# contactor_control.net
KiCad netlist of a schematic drawn in Altium Designer
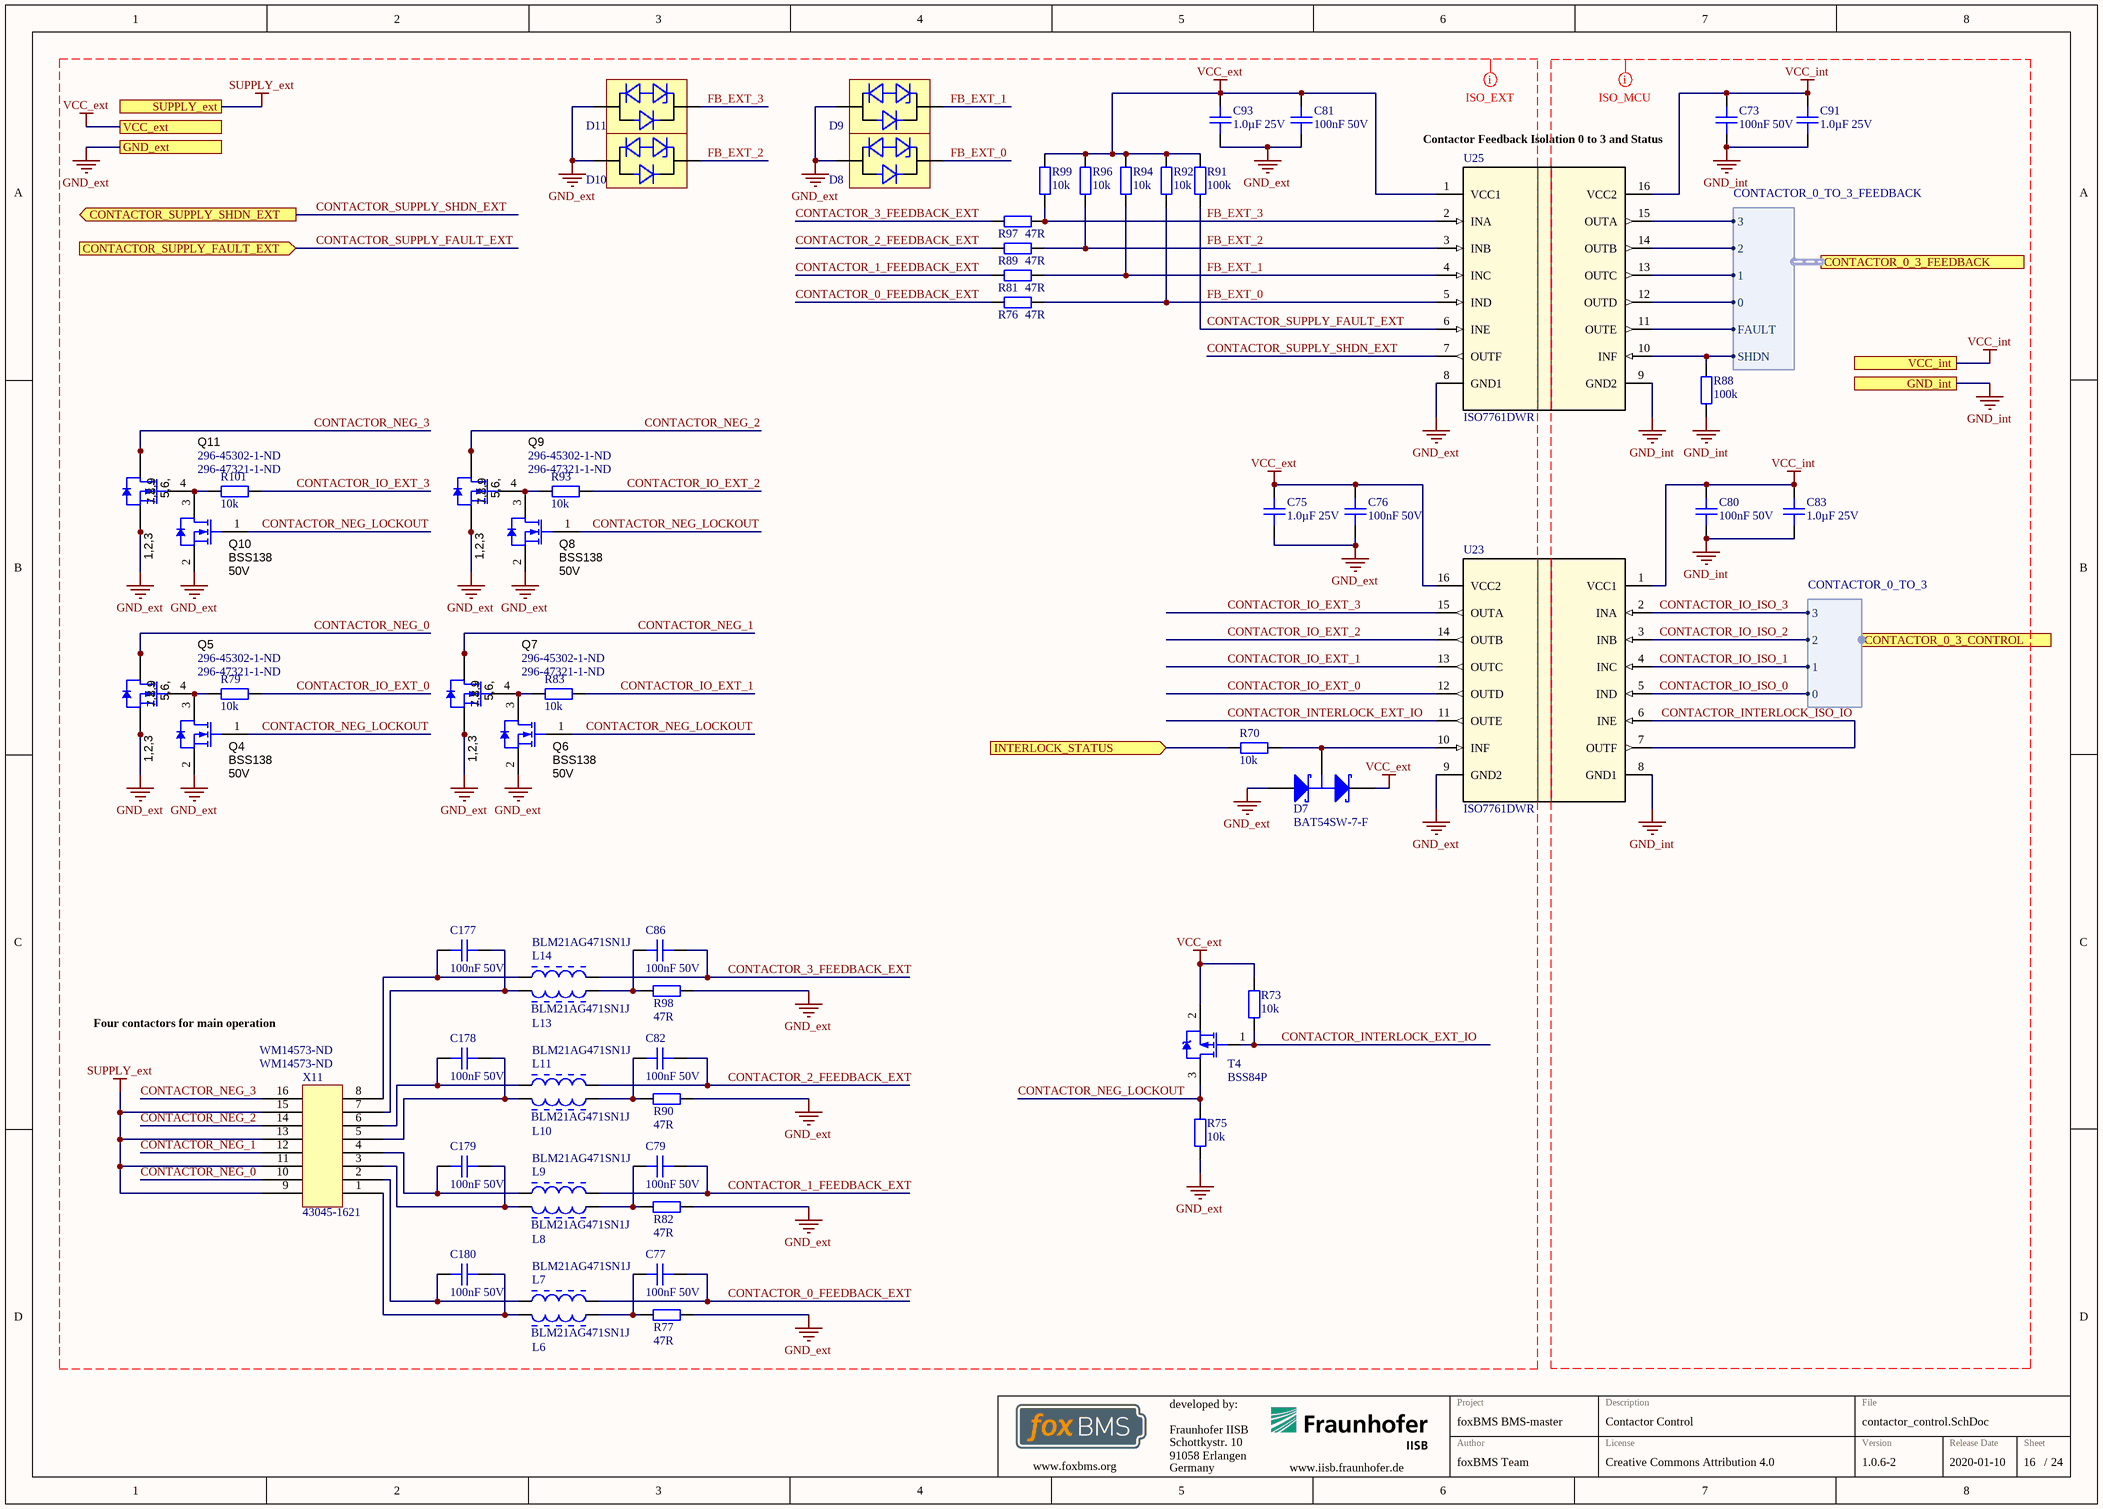
[diagram p0: contactor_control.SchDoc]

(export (version "E")
  (design (tool "Eeschema 10.0.6"))
  (components
    (comp (ref "C73")
      (value "100nF 50V")
      (footprint "0603C")
      (description "Ceramic, 100nF, ±10%, 50V, X7R, –55 to 125°C, 0603 (1608),RoHS, Automotive")
      (fields (field (name "PART NUMBER") "GCJ188R71H104KA12") (field (name "TOLERANCE") "±10%"))
      (libsource (lib "master-010106") (part "C"))
    )
    (comp (ref "C75")
      (value "1.0µF 25V")
      (footprint "0603C")
      (description "Ceramic, 1.0µF, ±10%, 25V, X7R, –55 to 125°C, 0603 (1608),RoHS, Automotive")
      (fields (field (name "PART NUMBER") "GCJ188R71E105KA01") (field (name "TOLERANCE") "±10%"))
      (libsource (lib "master-010106") (part "gen_C_ceramic_1u_25V_X7R_0603"))
    )
    (comp (ref "C76")
      (value "100nF 50V")
      (footprint "0603C")
      (description "Ceramic, 100nF, ±10%, 50V, X7R, –55 to 125°C, 0603 (1608),RoHS, Automotive")
      (fields (field (name "PART NUMBER") "GCJ188R71H104KA12") (field (name "TOLERANCE") "±10%"))
      (libsource (lib "master-010106") (part "C"))
    )
    (comp (ref "C77")
      (value "100nF 50V")
      (footprint "0603C")
      (description "Ceramic, 100nF, ±10%, 50V, X7R, –55 to 125°C, 0603 (1608),RoHS, Automotive")
      (fields (field (name "PART NUMBER") "GCJ188R71H104KA12") (field (name "TOLERANCE") "±10%"))
      (libsource (lib "master-010106") (part "C"))
    )
    (comp (ref "C79")
      (value "100nF 50V")
      (footprint "0603C")
      (description "Ceramic, 100nF, ±10%, 50V, X7R, –55 to 125°C, 0603 (1608),RoHS, Automotive")
      (fields (field (name "PART NUMBER") "GCJ188R71H104KA12") (field (name "TOLERANCE") "±10%"))
      (libsource (lib "master-010106") (part "C"))
    )
    (comp (ref "C80")
      (value "100nF 50V")
      (footprint "0603C")
      (description "Ceramic, 100nF, ±10%, 50V, X7R, –55 to 125°C, 0603 (1608),RoHS, Automotive")
      (fields (field (name "PART NUMBER") "GCJ188R71H104KA12") (field (name "TOLERANCE") "±10%"))
      (libsource (lib "master-010106") (part "C"))
    )
    (comp (ref "C81")
      (value "100nF 50V")
      (footprint "0603C")
      (description "Ceramic, 100nF, ±10%, 50V, X7R, –55 to 125°C, 0603 (1608),RoHS, Automotive")
      (fields (field (name "PART NUMBER") "GCJ188R71H104KA12") (field (name "TOLERANCE") "±10%"))
      (libsource (lib "master-010106") (part "C"))
    )
    (comp (ref "C82")
      (value "100nF 50V")
      (footprint "0603C")
      (description "Ceramic, 100nF, ±10%, 50V, X7R, –55 to 125°C, 0603 (1608),RoHS, Automotive")
      (fields (field (name "PART NUMBER") "GCJ188R71H104KA12") (field (name "TOLERANCE") "±10%"))
      (libsource (lib "master-010106") (part "C"))
    )
    (comp (ref "C83")
      (value "1.0µF 25V")
      (footprint "0603C")
      (description "Ceramic, 1.0µF, ±10%, 25V, X7R, –55 to 125°C, 0603 (1608),RoHS, Automotive")
      (fields (field (name "PART NUMBER") "GCJ188R71E105KA01") (field (name "TOLERANCE") "±10%"))
      (libsource (lib "master-010106") (part "gen_C_ceramic_1u_25V_X7R_0603"))
    )
    (comp (ref "C86")
      (value "100nF 50V")
      (footprint "0603C")
      (description "Ceramic, 100nF, ±10%, 50V, X7R, –55 to 125°C, 0603 (1608),RoHS, Automotive")
      (fields (field (name "PART NUMBER") "GCJ188R71H104KA12") (field (name "TOLERANCE") "±10%"))
      (libsource (lib "master-010106") (part "C"))
    )
    (comp (ref "C91")
      (value "1.0µF 25V")
      (footprint "0603C")
      (description "Ceramic, 1.0µF, ±10%, 25V, X7R, –55 to 125°C, 0603 (1608),RoHS, Automotive")
      (fields (field (name "PART NUMBER") "GCJ188R71E105KA01") (field (name "TOLERANCE") "±10%"))
      (libsource (lib "master-010106") (part "gen_C_ceramic_1u_25V_X7R_0603"))
    )
    (comp (ref "C93")
      (value "1.0µF 25V")
      (footprint "0603C")
      (description "Ceramic, 1.0µF, ±10%, 25V, X7R, –55 to 125°C, 0603 (1608),RoHS, Automotive")
      (fields (field (name "PART NUMBER") "GCJ188R71E105KA01") (field (name "TOLERANCE") "±10%"))
      (libsource (lib "master-010106") (part "gen_C_ceramic_1u_25V_X7R_0603"))
    )
    (comp (ref "C177")
      (value "100nF 50V")
      (footprint "0603C")
      (description "Ceramic, 100nF, ±10%, 50V, X7R, –55 to 125°C, 0603 (1608),RoHS, Automotive")
      (fields (field (name "PART NUMBER") "GCJ188R71H104KA12") (field (name "TOLERANCE") "±10%"))
      (libsource (lib "master-010106") (part "C"))
    )
    (comp (ref "C178")
      (value "100nF 50V")
      (footprint "0603C")
      (description "Ceramic, 100nF, ±10%, 50V, X7R, –55 to 125°C, 0603 (1608),RoHS, Automotive")
      (fields (field (name "PART NUMBER") "GCJ188R71H104KA12") (field (name "TOLERANCE") "±10%"))
      (libsource (lib "master-010106") (part "C"))
    )
    (comp (ref "C179")
      (value "100nF 50V")
      (footprint "0603C")
      (description "Ceramic, 100nF, ±10%, 50V, X7R, –55 to 125°C, 0603 (1608),RoHS, Automotive")
      (fields (field (name "PART NUMBER") "GCJ188R71H104KA12") (field (name "TOLERANCE") "±10%"))
      (libsource (lib "master-010106") (part "C"))
    )
    (comp (ref "C180")
      (value "100nF 50V")
      (footprint "0603C")
      (description "Ceramic, 100nF, ±10%, 50V, X7R, –55 to 125°C, 0603 (1608),RoHS, Automotive")
      (fields (field (name "PART NUMBER") "GCJ188R71H104KA12") (field (name "TOLERANCE") "±10%"))
      (libsource (lib "master-010106") (part "C"))
    )
    (comp (ref "D7")
      (value "BAT54SW-7-F")
      (footprint "DIOD-SOT323-3_V")
      (description "Schottky Barrier Diode, 30 V, 200 mA, -65 to 125 degC, 3-Pin SOT323, RoHS, Tape and Reel")
      (fields (field (name "MANUFACTURER") "DiodesIncorporated"))
      (libsource (lib "Altium Content Vault") (part "DSKY-AKC-3"))
    )
    (comp (ref "D8")
      (value "CDSOD323-T05")
      (footprint "SODFL250X110-2N")
      (description "TVS Diode, CDSOD323 Series, Unidirectional, 5 V, 18.3 V, SOD-323, 2 Pins")
      (fields (field (name "MANUFACTURER") "Bourns"))
      (libsource (lib "OE750") (part "D_TVS_uni"))
    )
    (comp (ref "D9")
      (value "CDSOD323-T05")
      (footprint "SODFL250X110-2N")
      (description "TVS Diode, CDSOD323 Series, Unidirectional, 5 V, 18.3 V, SOD-323, 2 Pins")
      (fields (field (name "MANUFACTURER") "Bourns"))
      (libsource (lib "OE750") (part "D_TVS_uni"))
    )
    (comp (ref "D10")
      (value "CDSOD323-T05")
      (footprint "SODFL250X110-2N")
      (description "TVS Diode, CDSOD323 Series, Unidirectional, 5 V, 18.3 V, SOD-323, 2 Pins")
      (fields (field (name "MANUFACTURER") "Bourns"))
      (libsource (lib "OE750") (part "D_TVS_uni"))
    )
    (comp (ref "D11")
      (value "CDSOD323-T05")
      (footprint "SODFL250X110-2N")
      (description "TVS Diode, CDSOD323 Series, Unidirectional, 5 V, 18.3 V, SOD-323, 2 Pins")
      (fields (field (name "MANUFACTURER") "Bourns"))
      (libsource (lib "OE750") (part "D_TVS_uni"))
    )
    (comp (ref "L6")
      (value "BLM21AG471SN1J")
      (footprint "MURA-BLM21-H1-CHIP-2_V")
      (fields (field (name "MANUFACTURER") "Murata"))
      (libsource (lib "") (part "MURA-FB-2_1"))
    )
    (comp (ref "L7")
      (value "BLM21AG471SN1J")
      (footprint "MURA-BLM21-H1-CHIP-2_V")
      (fields (field (name "MANUFACTURER") "Murata"))
      (libsource (lib "Altium Content Vault") (part "MURA-FB-2"))
    )
    (comp (ref "L8")
      (value "BLM21AG471SN1J")
      (footprint "MURA-BLM21-H1-CHIP-2_V")
      (fields (field (name "MANUFACTURER") "Murata"))
      (libsource (lib "") (part "MURA-FB-2_1"))
    )
    (comp (ref "L9")
      (value "BLM21AG471SN1J")
      (footprint "MURA-BLM21-H1-CHIP-2_V")
      (fields (field (name "MANUFACTURER") "Murata"))
      (libsource (lib "Altium Content Vault") (part "MURA-FB-2"))
    )
    (comp (ref "L10")
      (value "BLM21AG471SN1J")
      (footprint "MURA-BLM21-H1-CHIP-2_V")
      (fields (field (name "MANUFACTURER") "Murata"))
      (libsource (lib "") (part "MURA-FB-2_1"))
    )
    (comp (ref "L11")
      (value "BLM21AG471SN1J")
      (footprint "MURA-BLM21-H1-CHIP-2_V")
      (fields (field (name "MANUFACTURER") "Murata"))
      (libsource (lib "Altium Content Vault") (part "MURA-FB-2"))
    )
    (comp (ref "L13")
      (value "BLM21AG471SN1J")
      (footprint "MURA-BLM21-H1-CHIP-2_V")
      (fields (field (name "MANUFACTURER") "Murata"))
      (libsource (lib "") (part "MURA-FB-2_1"))
    )
    (comp (ref "L14")
      (value "BLM21AG471SN1J")
      (footprint "MURA-BLM21-H1-CHIP-2_V")
      (fields (field (name "MANUFACTURER") "Murata"))
      (libsource (lib "Altium Content Vault") (part "MURA-FB-2"))
    )
    (comp (ref "Q4")
      (value "BSS138")
      (footprint "SOT-23")
      (description "MOSFET, N-CH, 50V, 0.22A, SOT-23")
      (fields
        (field (name "MANUFACTURER") "Fairchild Semiconductor")
        (field (name "ALTIUM_VALUE") "50V")
        (field (name "PUBLISHER") "Texas Instruments")
      )
      (libsource (lib "master-010106") (part "BSS138"))
    )
    (comp (ref "Q5")
      (value "CSD18543Q3A")
      (footprint "SONQ3A")
      (description "60V, N ch NexFET MOSFET™, single SON3x3, 9.9mOhm")
      (fields
        (field (name "MANUFACTURER") "Texas Instruments")
        (field (name "SUPPLIER PART NUMBER 1") "296-45302-1-ND")
        (field (name "SUPPLIER PART NUMBER 2") "296-47321-1-ND")
        (field (name "PUBLISHER") "Texas Instruments")
      )
      (libsource (lib "master-010106") (part "CSD18543Q3A"))
    )
    (comp (ref "Q6")
      (value "BSS138")
      (footprint "SOT-23")
      (description "MOSFET, N-CH, 50V, 0.22A, SOT-23")
      (fields
        (field (name "MANUFACTURER") "Fairchild Semiconductor")
        (field (name "ALTIUM_VALUE") "50V")
        (field (name "PUBLISHER") "Texas Instruments")
      )
      (libsource (lib "master-010106") (part "BSS138"))
    )
    (comp (ref "Q7")
      (value "CSD18543Q3A")
      (footprint "SONQ3A")
      (description "60V, N ch NexFET MOSFET™, single SON3x3, 9.9mOhm")
      (fields
        (field (name "MANUFACTURER") "Texas Instruments")
        (field (name "SUPPLIER PART NUMBER 1") "296-45302-1-ND")
        (field (name "SUPPLIER PART NUMBER 2") "296-47321-1-ND")
        (field (name "PUBLISHER") "Texas Instruments")
      )
      (libsource (lib "master-010106") (part "CSD18543Q3A"))
    )
    (comp (ref "Q8")
      (value "BSS138")
      (footprint "SOT-23")
      (description "MOSFET, N-CH, 50V, 0.22A, SOT-23")
      (fields
        (field (name "MANUFACTURER") "Fairchild Semiconductor")
        (field (name "ALTIUM_VALUE") "50V")
        (field (name "PUBLISHER") "Texas Instruments")
      )
      (libsource (lib "master-010106") (part "BSS138"))
    )
    (comp (ref "Q9")
      (value "CSD18543Q3A")
      (footprint "SONQ3A")
      (description "60V, N ch NexFET MOSFET™, single SON3x3, 9.9mOhm")
      (fields
        (field (name "MANUFACTURER") "Texas Instruments")
        (field (name "SUPPLIER PART NUMBER 1") "296-45302-1-ND")
        (field (name "SUPPLIER PART NUMBER 2") "296-47321-1-ND")
        (field (name "PUBLISHER") "Texas Instruments")
      )
      (libsource (lib "master-010106") (part "CSD18543Q3A"))
    )
    (comp (ref "Q10")
      (value "BSS138")
      (footprint "SOT-23")
      (description "MOSFET, N-CH, 50V, 0.22A, SOT-23")
      (fields
        (field (name "MANUFACTURER") "Fairchild Semiconductor")
        (field (name "ALTIUM_VALUE") "50V")
        (field (name "PUBLISHER") "Texas Instruments")
      )
      (libsource (lib "master-010106") (part "BSS138"))
    )
    (comp (ref "Q11")
      (value "CSD18543Q3A")
      (footprint "SONQ3A")
      (description "60V, N ch NexFET MOSFET™, single SON3x3, 9.9mOhm")
      (fields
        (field (name "MANUFACTURER") "Texas Instruments")
        (field (name "SUPPLIER PART NUMBER 1") "296-45302-1-ND")
        (field (name "SUPPLIER PART NUMBER 2") "296-47321-1-ND")
        (field (name "PUBLISHER") "Texas Instruments")
      )
      (libsource (lib "master-010106") (part "CSD18543Q3A"))
    )
    (comp (ref "R70")
      (value "10k")
      (footprint "0603R")
      (description "SMD Resistor 10k 0603")
      (fields (field (name "PART NUMBER") "gen_R_10k_0603") (field (name "TOLERANCE") "1%"))
      (libsource (lib "master-010106") (part "R"))
    )
    (comp (ref "R73")
      (value "10k")
      (footprint "0603R")
      (description "SMD Resistor 10k 0603")
      (fields (field (name "PART NUMBER") "gen_R_10k_0603") (field (name "TOLERANCE") "1%"))
      (libsource (lib "master-010106") (part "R"))
    )
    (comp (ref "R75")
      (value "10k")
      (footprint "0603R")
      (description "SMD Resistor 10k 0603")
      (fields (field (name "PART NUMBER") "gen_R_10k_0603") (field (name "TOLERANCE") "1%"))
      (libsource (lib "master-010106") (part "R"))
    )
    (comp (ref "R76")
      (value "47R")
      (footprint "0603R")
      (description "SMD Resistor 47R 0603")
      (fields (field (name "PART NUMBER") "gen_R_47R_0603") (field (name "TOLERANCE") "1%"))
      (libsource (lib "master-010106") (part "R"))
    )
    (comp (ref "R77")
      (value "47R")
      (footprint "0603R")
      (description "SMD Resistor 47R 0603")
      (fields (field (name "PART NUMBER") "gen_R_47R_0603") (field (name "TOLERANCE") "1%"))
      (libsource (lib "master-010106") (part "R"))
    )
    (comp (ref "R79")
      (value "10k")
      (footprint "0603R")
      (description "SMD Resistor 10k 0603")
      (fields (field (name "PART NUMBER") "gen_R_10k_0603") (field (name "TOLERANCE") "1%"))
      (libsource (lib "master-010106") (part "R"))
    )
    (comp (ref "R81")
      (value "47R")
      (footprint "0603R")
      (description "SMD Resistor 47R 0603")
      (fields (field (name "PART NUMBER") "gen_R_47R_0603") (field (name "TOLERANCE") "1%"))
      (libsource (lib "master-010106") (part "R"))
    )
    (comp (ref "R82")
      (value "47R")
      (footprint "0603R")
      (description "SMD Resistor 47R 0603")
      (fields (field (name "PART NUMBER") "gen_R_47R_0603") (field (name "TOLERANCE") "1%"))
      (libsource (lib "master-010106") (part "R"))
    )
    (comp (ref "R83")
      (value "10k")
      (footprint "0603R")
      (description "SMD Resistor 10k 0603")
      (fields (field (name "PART NUMBER") "gen_R_10k_0603") (field (name "TOLERANCE") "1%"))
      (libsource (lib "master-010106") (part "R"))
    )
    (comp (ref "R88")
      (value "100k")
      (footprint "0603R")
      (description "SMD Resistor 100k 0603")
      (fields (field (name "PART NUMBER") "gen_R_100k_0603"))
      (libsource (lib "master-010106") (part "gen_R_100k_0603"))
    )
    (comp (ref "R89")
      (value "47R")
      (footprint "0603R")
      (description "SMD Resistor 47R 0603")
      (fields (field (name "PART NUMBER") "gen_R_47R_0603") (field (name "TOLERANCE") "1%"))
      (libsource (lib "master-010106") (part "R"))
    )
    (comp (ref "R90")
      (value "47R")
      (footprint "0603R")
      (description "SMD Resistor 47R 0603")
      (fields (field (name "PART NUMBER") "gen_R_47R_0603") (field (name "TOLERANCE") "1%"))
      (libsource (lib "master-010106") (part "R"))
    )
    (comp (ref "R91")
      (value "100k")
      (footprint "0603R")
      (description "SMD Resistor 100k 0603")
      (fields (field (name "PART NUMBER") "gen_R_100k_0603"))
      (libsource (lib "master-010106") (part "gen_R_100k_0603"))
    )
    (comp (ref "R92")
      (value "10k")
      (footprint "0603R")
      (description "SMD Resistor 10k 0603")
      (fields (field (name "PART NUMBER") "gen_R_10k_0603") (field (name "TOLERANCE") "1%"))
      (libsource (lib "master-010106") (part "R"))
    )
    (comp (ref "R93")
      (value "10k")
      (footprint "0603R")
      (description "SMD Resistor 10k 0603")
      (fields (field (name "PART NUMBER") "gen_R_10k_0603") (field (name "TOLERANCE") "1%"))
      (libsource (lib "master-010106") (part "R"))
    )
    (comp (ref "R94")
      (value "10k")
      (footprint "0603R")
      (description "SMD Resistor 10k 0603")
      (fields (field (name "PART NUMBER") "gen_R_10k_0603") (field (name "TOLERANCE") "1%"))
      (libsource (lib "master-010106") (part "R"))
    )
    (comp (ref "R96")
      (value "10k")
      (footprint "0603R")
      (description "SMD Resistor 10k 0603")
      (fields (field (name "PART NUMBER") "gen_R_10k_0603") (field (name "TOLERANCE") "1%"))
      (libsource (lib "master-010106") (part "R"))
    )
    (comp (ref "R97")
      (value "47R")
      (footprint "0603R")
      (description "SMD Resistor 47R 0603")
      (fields (field (name "PART NUMBER") "gen_R_47R_0603") (field (name "TOLERANCE") "1%"))
      (libsource (lib "master-010106") (part "R"))
    )
    (comp (ref "R98")
      (value "47R")
      (footprint "0603R")
      (description "SMD Resistor 47R 0603")
      (fields (field (name "PART NUMBER") "gen_R_47R_0603") (field (name "TOLERANCE") "1%"))
      (libsource (lib "master-010106") (part "R"))
    )
    (comp (ref "R99")
      (value "10k")
      (footprint "0603R")
      (description "SMD Resistor 10k 0603")
      (fields (field (name "PART NUMBER") "gen_R_10k_0603") (field (name "TOLERANCE") "1%"))
      (libsource (lib "master-010106") (part "R"))
    )
    (comp (ref "R101")
      (value "10k")
      (footprint "0603R")
      (description "SMD Resistor 10k 0603")
      (fields (field (name "PART NUMBER") "gen_R_10k_0603") (field (name "TOLERANCE") "1%"))
      (libsource (lib "master-010106") (part "R"))
    )
    (comp (ref "T4")
      (value "BSS84P")
      (footprint "INF-PG-SOT23_N")
      (fields (field (name "MANUFACTURER") "Infineon"))
      (libsource (lib "Altium Content Vault") (part "INF-PEMOS-GSD-3-B"))
    )
    (comp (ref "U23")
      (value "ISO7761DWR")
      (footprint "DW0016B_N")
      (description "Imported")
      (fields (field (name "MANUFACTURER") "Texas Instruments"))
      (libsource (lib "ti-import") (part "ISO7761DWR"))
    )
    (comp (ref "U25")
      (value "ISO7761DWR")
      (footprint "DW0016B_N")
      (description "Imported")
      (fields (field (name "MANUFACTURER") "Texas Instruments"))
      (libsource (lib "") (part "ISO7761DWR_1"))
    )
    (comp (ref "X11")
      (value "43045-1621")
      (footprint "43045-1621")
      (fields
        (field (name "PART NUMBER") "molex_microfit_3_08x2_THT")
        (field (name "MANUFACTURER") "Molex")
        (field (name "SUPPLIER PART NUMBER 1") "WM14573-ND")
        (field (name "SUPPLIER PART NUMBER 2") "WM14573-ND")
      )
      (libsource (lib "master-010106") (part "molex_microfit_3_08x2_THT"))
    )
  )
  (nets
    (net (code "3") (name "/CONTACTOR_0_FEEDBACK_EXT") (class "Default")
      (node (ref "C77") (pin "2") (pinfunction "2_2") (pintype "passive"))
      (node (ref "L7") (pin "2") (pinfunction "2_2") (pintype "passive"))
      (node (ref "R76") (pin "1") (pinfunction "1_1") (pintype "passive"))
    )
    (net (code "4") (name "/CONTACTOR_1_FEEDBACK_EXT") (class "Default")
      (node (ref "C79") (pin "2") (pinfunction "2_2") (pintype "passive"))
      (node (ref "L9") (pin "2") (pinfunction "2_2") (pintype "passive"))
      (node (ref "R81") (pin "1") (pinfunction "1_1") (pintype "passive"))
    )
    (net (code "5") (name "/CONTACTOR_2_FEEDBACK_EXT") (class "Default")
      (node (ref "C82") (pin "2") (pinfunction "2_2") (pintype "passive"))
      (node (ref "L11") (pin "2") (pinfunction "2_2") (pintype "passive"))
      (node (ref "R89") (pin "1") (pinfunction "1_1") (pintype "passive"))
    )
    (net (code "6") (name "/CONTACTOR_3_FEEDBACK_EXT") (class "Default")
      (node (ref "C86") (pin "2") (pinfunction "2_2") (pintype "passive"))
      (node (ref "L14") (pin "2") (pinfunction "2_2") (pintype "passive"))
      (node (ref "R97") (pin "2") (pinfunction "2_2") (pintype "passive"))
    )
    (net (code "7") (name "/CONTACTOR_INTERLOCK_EXT_IO") (class "Default")
      (node (ref "R73") (pin "1") (pinfunction "1_1") (pintype "passive"))
      (node (ref "T4") (pin "1") (pinfunction "GATE_1") (pintype "passive"))
      (node (ref "U23") (pin "11") (pinfunction "OUTE_11") (pintype "output"))
    )
    (net (code "8") (name "/CONTACTOR_INTERLOCK_ISO_IO") (class "Default")
      (node (ref "U23") (pin "6") (pinfunction "INE_6") (pintype "input"))
      (node (ref "U23") (pin "7") (pinfunction "OUTF_7") (pintype "output"))
    )
    (net (code "9") (name "/CONTACTOR_IO_EXT_0") (class "Default")
      (node (ref "R79") (pin "1") (pinfunction "1_1") (pintype "passive"))
      (node (ref "U23") (pin "12") (pinfunction "OUTD_12") (pintype "output"))
    )
    (net (code "10") (name "/CONTACTOR_IO_EXT_1") (class "Default")
      (node (ref "R83") (pin "1") (pinfunction "1_1") (pintype "passive"))
      (node (ref "U23") (pin "13") (pinfunction "OUTC_13") (pintype "output"))
    )
    (net (code "11") (name "/CONTACTOR_IO_EXT_2") (class "Default")
      (node (ref "R93") (pin "1") (pinfunction "1_1") (pintype "passive"))
      (node (ref "U23") (pin "14") (pinfunction "OUTB_14") (pintype "output"))
    )
    (net (code "12") (name "/CONTACTOR_IO_EXT_3") (class "Default")
      (node (ref "R101") (pin "1") (pinfunction "1_1") (pintype "passive"))
      (node (ref "U23") (pin "15") (pinfunction "OUTA_15") (pintype "output"))
    )
    (net (code "13") (name "/CONTACTOR_IO_ISO_0") (class "Default")
      (node (ref "U23") (pin "5") (pinfunction "IND_5") (pintype "input"))
    )
    (net (code "14") (name "/CONTACTOR_IO_ISO_1") (class "Default")
      (node (ref "U23") (pin "4") (pinfunction "INC_4") (pintype "input"))
    )
    (net (code "15") (name "/CONTACTOR_IO_ISO_2") (class "Default")
      (node (ref "U23") (pin "3") (pinfunction "INB_3") (pintype "input"))
    )
    (net (code "16") (name "/CONTACTOR_IO_ISO_3") (class "Default")
      (node (ref "U23") (pin "2") (pinfunction "INA_2") (pintype "input"))
    )
    (net (code "17") (name "/CONTACTOR_NEG_0") (class "Default")
      (node (ref "Q5") (pin "5") (pinfunction "D_5") (pintype "passive"))
      (node (ref "Q5") (pin "6") (pinfunction "D_6") (pintype "passive"))
      (node (ref "Q5") (pin "7") (pinfunction "D_7") (pintype "passive"))
      (node (ref "Q5") (pin "8") (pinfunction "D_8") (pintype "passive"))
      (node (ref "Q5") (pin "9") (pinfunction "D_9") (pintype "passive"))
      (node (ref "X11") (pin "10") (pintype "passive"))
    )
    (net (code "18") (name "/CONTACTOR_NEG_1") (class "Default")
      (node (ref "Q7") (pin "5") (pinfunction "D_5") (pintype "passive"))
      (node (ref "Q7") (pin "6") (pinfunction "D_6") (pintype "passive"))
      (node (ref "Q7") (pin "7") (pinfunction "D_7") (pintype "passive"))
      (node (ref "Q7") (pin "8") (pinfunction "D_8") (pintype "passive"))
      (node (ref "Q7") (pin "9") (pinfunction "D_9") (pintype "passive"))
      (node (ref "X11") (pin "12") (pintype "passive"))
    )
    (net (code "19") (name "/CONTACTOR_NEG_2") (class "Default")
      (node (ref "Q9") (pin "5") (pinfunction "D_5") (pintype "passive"))
      (node (ref "Q9") (pin "6") (pinfunction "D_6") (pintype "passive"))
      (node (ref "Q9") (pin "7") (pinfunction "D_7") (pintype "passive"))
      (node (ref "Q9") (pin "8") (pinfunction "D_8") (pintype "passive"))
      (node (ref "Q9") (pin "9") (pinfunction "D_9") (pintype "passive"))
      (node (ref "X11") (pin "14") (pintype "passive"))
    )
    (net (code "20") (name "/CONTACTOR_NEG_3") (class "Default")
      (node (ref "Q11") (pin "5") (pinfunction "D_5") (pintype "passive"))
      (node (ref "Q11") (pin "6") (pinfunction "D_6") (pintype "passive"))
      (node (ref "Q11") (pin "7") (pinfunction "D_7") (pintype "passive"))
      (node (ref "Q11") (pin "8") (pinfunction "D_8") (pintype "passive"))
      (node (ref "Q11") (pin "9") (pinfunction "D_9") (pintype "passive"))
      (node (ref "X11") (pin "16") (pintype "passive"))
    )
    (net (code "21") (name "/CONTACTOR_NEG_LOCKOUT") (class "Default")
      (node (ref "Q10") (pin "1") (pinfunction "G_1") (pintype "passive"))
      (node (ref "Q4") (pin "1") (pinfunction "G_1") (pintype "passive"))
      (node (ref "Q6") (pin "1") (pinfunction "G_1") (pintype "passive"))
      (node (ref "Q8") (pin "1") (pinfunction "G_1") (pintype "passive"))
      (node (ref "R75") (pin "2") (pinfunction "2_2") (pintype "passive"))
      (node (ref "T4") (pin "3") (pinfunction "DRAIN_3") (pintype "passive"))
    )
    (net (code "22") (name "/CONTACTOR_SUPPLY_FAULT_EXT") (class "Default")
      (node (ref "R91") (pin "1") (pinfunction "1_1") (pintype "passive"))
      (node (ref "U25") (pin "6") (pinfunction "INE_6") (pintype "input"))
    )
    (net (code "23") (name "/CONTACTOR_SUPPLY_SHDN_EXT") (class "Default")
      (node (ref "U25") (pin "7") (pinfunction "OUTF_7") (pintype "output"))
    )
    (net (code "24") (name "/FAULT") (class "Default")
      (node (ref "U25") (pin "11") (pinfunction "OUTE_11") (pintype "output"))
    )
    (net (code "25") (name "/FB_EXT_0") (class "Default")
      (node (ref "D8") (pin "1") (pinfunction "K_1") (pintype "passive"))
      (node (ref "R76") (pin "2") (pinfunction "2_2") (pintype "passive"))
      (node (ref "R92") (pin "1") (pinfunction "1_1") (pintype "passive"))
      (node (ref "U25") (pin "5") (pinfunction "IND_5") (pintype "input"))
    )
    (net (code "26") (name "/FB_EXT_1") (class "Default")
      (node (ref "D9") (pin "1") (pinfunction "K_1") (pintype "passive"))
      (node (ref "R81") (pin "2") (pinfunction "2_2") (pintype "passive"))
      (node (ref "R94") (pin "1") (pinfunction "1_1") (pintype "passive"))
      (node (ref "U25") (pin "4") (pinfunction "INC_4") (pintype "input"))
    )
    (net (code "27") (name "/FB_EXT_2") (class "Default")
      (node (ref "D10") (pin "1") (pinfunction "K_1") (pintype "passive"))
      (node (ref "R89") (pin "2") (pinfunction "2_2") (pintype "passive"))
      (node (ref "R96") (pin "1") (pinfunction "1_1") (pintype "passive"))
      (node (ref "U25") (pin "3") (pinfunction "INB_3") (pintype "input"))
    )
    (net (code "28") (name "/FB_EXT_3") (class "Default")
      (node (ref "D11") (pin "1") (pinfunction "K_1") (pintype "passive"))
      (node (ref "R97") (pin "1") (pinfunction "1_1") (pintype "passive"))
      (node (ref "R99") (pin "1") (pinfunction "1_1") (pintype "passive"))
      (node (ref "U25") (pin "2") (pinfunction "INA_2") (pintype "input"))
    )
    (net (code "29") (name "/INTERLOCK_STATUS") (class "Default")
      (node (ref "R70") (pin "2") (pinfunction "2_2") (pintype "passive"))
    )
    (net (code "30") (name "/SHDN") (class "Default")
      (node (ref "R88") (pin "2") (pinfunction "2_2") (pintype "passive"))
      (node (ref "U25") (pin "10") (pinfunction "INF_10") (pintype "input"))
    )
    (net (code "33") (name "GND_ext") (class "Default")
      (node (ref "C75") (pin "2") (pinfunction "2_2") (pintype "passive"))
      (node (ref "C76") (pin "2") (pinfunction "2_2") (pintype "passive"))
      (node (ref "C81") (pin "2") (pinfunction "2_2") (pintype "passive"))
      (node (ref "C93") (pin "2") (pinfunction "2_2") (pintype "passive"))
      (node (ref "D10") (pin "2") (pinfunction "A_2") (pintype "passive"))
      (node (ref "D11") (pin "2") (pinfunction "A_2") (pintype "passive"))
      (node (ref "D7") (pin "1") (pinfunction "A_1") (pintype "passive"))
      (node (ref "D8") (pin "2") (pinfunction "A_2") (pintype "passive"))
      (node (ref "D9") (pin "2") (pinfunction "A_2") (pintype "passive"))
      (node (ref "Q10") (pin "2") (pinfunction "S_2") (pintype "passive"))
      (node (ref "Q11") (pin "1") (pinfunction "S_1") (pintype "passive"))
      (node (ref "Q11") (pin "2") (pinfunction "S_2") (pintype "passive"))
      (node (ref "Q11") (pin "3") (pinfunction "S_3") (pintype "passive"))
      (node (ref "Q4") (pin "2") (pinfunction "S_2") (pintype "passive"))
      (node (ref "Q5") (pin "1") (pinfunction "S_1") (pintype "passive"))
      (node (ref "Q5") (pin "2") (pinfunction "S_2") (pintype "passive"))
      (node (ref "Q5") (pin "3") (pinfunction "S_3") (pintype "passive"))
      (node (ref "Q6") (pin "2") (pinfunction "S_2") (pintype "passive"))
      (node (ref "Q7") (pin "1") (pinfunction "S_1") (pintype "passive"))
      (node (ref "Q7") (pin "2") (pinfunction "S_2") (pintype "passive"))
      (node (ref "Q7") (pin "3") (pinfunction "S_3") (pintype "passive"))
      (node (ref "Q8") (pin "2") (pinfunction "S_2") (pintype "passive"))
      (node (ref "Q9") (pin "1") (pinfunction "S_1") (pintype "passive"))
      (node (ref "Q9") (pin "2") (pinfunction "S_2") (pintype "passive"))
      (node (ref "Q9") (pin "3") (pinfunction "S_3") (pintype "passive"))
      (node (ref "R75") (pin "1") (pinfunction "1_1") (pintype "passive"))
      (node (ref "R77") (pin "2") (pinfunction "2_2") (pintype "passive"))
      (node (ref "R82") (pin "2") (pinfunction "2_2") (pintype "passive"))
      (node (ref "R90") (pin "2") (pinfunction "2_2") (pintype "passive"))
      (node (ref "R98") (pin "2") (pinfunction "2_2") (pintype "passive"))
      (node (ref "U23") (pin "9") (pinfunction "GND2_9") (pintype "power_in"))
      (node (ref "U25") (pin "8") (pinfunction "GND1_8") (pintype "power_in"))
    )
    (net (code "34") (name "GND_int") (class "Default")
      (node (ref "C73") (pin "2") (pinfunction "2_2") (pintype "passive"))
      (node (ref "C80") (pin "2") (pinfunction "2_2") (pintype "passive"))
      (node (ref "C83") (pin "2") (pinfunction "2_2") (pintype "passive"))
      (node (ref "C91") (pin "2") (pinfunction "2_2") (pintype "passive"))
      (node (ref "R88") (pin "1") (pinfunction "1_1") (pintype "passive"))
      (node (ref "U23") (pin "8") (pinfunction "GND1_8") (pintype "power_in"))
      (node (ref "U25") (pin "9") (pinfunction "GND2_9") (pintype "power_in"))
    )
    (net (code "35") (name "Net-(C77-Pad1)") (class "Default")
      (node (ref "C77") (pin "1") (pinfunction "1_1") (pintype "passive"))
      (node (ref "L6") (pin "2") (pinfunction "2_2") (pintype "passive"))
      (node (ref "R77") (pin "1") (pinfunction "1_1") (pintype "passive"))
    )
    (net (code "36") (name "Net-(C79-Pad1)") (class "Default")
      (node (ref "C79") (pin "1") (pinfunction "1_1") (pintype "passive"))
      (node (ref "L8") (pin "2") (pinfunction "2_2") (pintype "passive"))
      (node (ref "R82") (pin "1") (pinfunction "1_1") (pintype "passive"))
    )
    (net (code "37") (name "Net-(C82-Pad1)") (class "Default")
      (node (ref "C82") (pin "1") (pinfunction "1_1") (pintype "passive"))
      (node (ref "L10") (pin "2") (pinfunction "2_2") (pintype "passive"))
      (node (ref "R90") (pin "1") (pinfunction "1_1") (pintype "passive"))
    )
    (net (code "38") (name "Net-(C86-Pad1)") (class "Default")
      (node (ref "C86") (pin "1") (pinfunction "1_1") (pintype "passive"))
      (node (ref "L13") (pin "2") (pinfunction "2_2") (pintype "passive"))
      (node (ref "R98") (pin "1") (pinfunction "1_1") (pintype "passive"))
    )
    (net (code "39") (name "Net-(C177-Pad1)") (class "Default")
      (node (ref "C177") (pin "1") (pinfunction "1_1") (pintype "passive"))
      (node (ref "L14") (pin "1") (pinfunction "1_1") (pintype "passive"))
      (node (ref "X11") (pin "8") (pintype "passive"))
    )
    (net (code "40") (name "Net-(C177-Pad2)") (class "Default")
      (node (ref "C177") (pin "2") (pinfunction "2_2") (pintype "passive"))
      (node (ref "L13") (pin "1") (pinfunction "1_1") (pintype "passive"))
      (node (ref "X11") (pin "7") (pintype "passive"))
    )
    (net (code "41") (name "Net-(C178-Pad1)") (class "Default")
      (node (ref "C178") (pin "1") (pinfunction "1_1") (pintype "passive"))
      (node (ref "L11") (pin "1") (pinfunction "1_1") (pintype "passive"))
      (node (ref "X11") (pin "6") (pintype "passive"))
    )
    (net (code "42") (name "Net-(C178-Pad2)") (class "Default")
      (node (ref "C178") (pin "2") (pinfunction "2_2") (pintype "passive"))
      (node (ref "L10") (pin "1") (pinfunction "1_1") (pintype "passive"))
      (node (ref "X11") (pin "5") (pintype "passive"))
    )
    (net (code "43") (name "Net-(C179-Pad1)") (class "Default")
      (node (ref "C179") (pin "1") (pinfunction "1_1") (pintype "passive"))
      (node (ref "L9") (pin "1") (pinfunction "1_1") (pintype "passive"))
      (node (ref "X11") (pin "4") (pintype "passive"))
    )
    (net (code "44") (name "Net-(C179-Pad2)") (class "Default")
      (node (ref "C179") (pin "2") (pinfunction "2_2") (pintype "passive"))
      (node (ref "L8") (pin "1") (pinfunction "1_1") (pintype "passive"))
      (node (ref "X11") (pin "3") (pintype "passive"))
    )
    (net (code "45") (name "Net-(C180-Pad1)") (class "Default")
      (node (ref "C180") (pin "1") (pinfunction "1_1") (pintype "passive"))
      (node (ref "L7") (pin "1") (pinfunction "1_1") (pintype "passive"))
      (node (ref "X11") (pin "2") (pintype "passive"))
    )
    (net (code "46") (name "Net-(C180-Pad2)") (class "Default")
      (node (ref "C180") (pin "2") (pinfunction "2_2") (pintype "passive"))
      (node (ref "L6") (pin "1") (pinfunction "1_1") (pintype "passive"))
      (node (ref "X11") (pin "1") (pintype "passive"))
    )
    (net (code "47") (name "Net-(D7-C)") (class "Default")
      (node (ref "D7") (pin "3") (pinfunction "C_3") (pintype "passive"))
      (node (ref "R70") (pin "1") (pinfunction "1_1") (pintype "passive"))
      (node (ref "U23") (pin "10") (pinfunction "INF_10") (pintype "input"))
    )
    (net (code "48") (name "Net-(Q4-D)") (class "Default")
      (node (ref "Q4") (pin "3") (pinfunction "D_3") (pintype "passive"))
      (node (ref "Q5") (pin "4") (pinfunction "G_4") (pintype "passive"))
      (node (ref "R79") (pin "2") (pinfunction "2_2") (pintype "passive"))
    )
    (net (code "49") (name "Net-(Q6-D)") (class "Default")
      (node (ref "Q6") (pin "3") (pinfunction "D_3") (pintype "passive"))
      (node (ref "Q7") (pin "4") (pinfunction "G_4") (pintype "passive"))
      (node (ref "R83") (pin "2") (pinfunction "2_2") (pintype "passive"))
    )
    (net (code "50") (name "Net-(Q8-D)") (class "Default")
      (node (ref "Q8") (pin "3") (pinfunction "D_3") (pintype "passive"))
      (node (ref "Q9") (pin "4") (pinfunction "G_4") (pintype "passive"))
      (node (ref "R93") (pin "2") (pinfunction "2_2") (pintype "passive"))
    )
    (net (code "51") (name "Net-(Q10-D)") (class "Default")
      (node (ref "Q10") (pin "3") (pinfunction "D_3") (pintype "passive"))
      (node (ref "Q11") (pin "4") (pinfunction "G_4") (pintype "passive"))
      (node (ref "R101") (pin "2") (pinfunction "2_2") (pintype "passive"))
    )
    (net (code "52") (name "SUPPLY_ext") (class "Default")
      (node (ref "X11") (pin "11") (pintype "passive"))
      (node (ref "X11") (pin "13") (pintype "passive"))
      (node (ref "X11") (pin "15") (pintype "passive"))
      (node (ref "X11") (pin "9") (pintype "passive"))
    )
    (net (code "53") (name "VCC_ext") (class "Default")
      (node (ref "C75") (pin "1") (pinfunction "1_1") (pintype "passive"))
      (node (ref "C76") (pin "1") (pinfunction "1_1") (pintype "passive"))
      (node (ref "C81") (pin "1") (pinfunction "1_1") (pintype "passive"))
      (node (ref "C93") (pin "1") (pinfunction "1_1") (pintype "passive"))
      (node (ref "D7") (pin "2") (pinfunction "K_2") (pintype "passive"))
      (node (ref "R73") (pin "2") (pinfunction "2_2") (pintype "passive"))
      (node (ref "R91") (pin "2") (pinfunction "2_2") (pintype "passive"))
      (node (ref "R92") (pin "2") (pinfunction "2_2") (pintype "passive"))
      (node (ref "R94") (pin "2") (pinfunction "2_2") (pintype "passive"))
      (node (ref "R96") (pin "2") (pinfunction "2_2") (pintype "passive"))
      (node (ref "R99") (pin "2") (pinfunction "2_2") (pintype "passive"))
      (node (ref "T4") (pin "2") (pinfunction "SOURCE_2") (pintype "passive"))
      (node (ref "U23") (pin "16") (pinfunction "VCC2_16") (pintype "power_in"))
      (node (ref "U25") (pin "1") (pinfunction "VCC1_1") (pintype "power_in"))
    )
    (net (code "54") (name "VCC_int") (class "Default")
      (node (ref "C73") (pin "1") (pinfunction "1_1") (pintype "passive"))
      (node (ref "C80") (pin "1") (pinfunction "1_1") (pintype "passive"))
      (node (ref "C83") (pin "1") (pinfunction "1_1") (pintype "passive"))
      (node (ref "C91") (pin "1") (pinfunction "1_1") (pintype "passive"))
      (node (ref "U23") (pin "1") (pinfunction "VCC1_1") (pintype "power_in"))
      (node (ref "U25") (pin "16") (pinfunction "VCC2_16") (pintype "power_in"))
    )
    (net (code "55") (name "unconnected-(U25-OUTA-Pad15)") (class "Default")
      (node (ref "U25") (pin "15") (pinfunction "OUTA_15") (pintype "output"))
    )
    (net (code "56") (name "unconnected-(U25-OUTB-Pad14)") (class "Default")
      (node (ref "U25") (pin "14") (pinfunction "OUTB_14") (pintype "output"))
    )
    (net (code "57") (name "unconnected-(U25-OUTC-Pad13)") (class "Default")
      (node (ref "U25") (pin "13") (pinfunction "OUTC_13") (pintype "output"))
    )
    (net (code "58") (name "unconnected-(U25-OUTD-Pad12)") (class "Default")
      (node (ref "U25") (pin "12") (pinfunction "OUTD_12") (pintype "output"))
    )
  )
)
